# MCU_-_STM32F407VGT6.net
KiCad netlist of a schematic drawn in Altium Designer
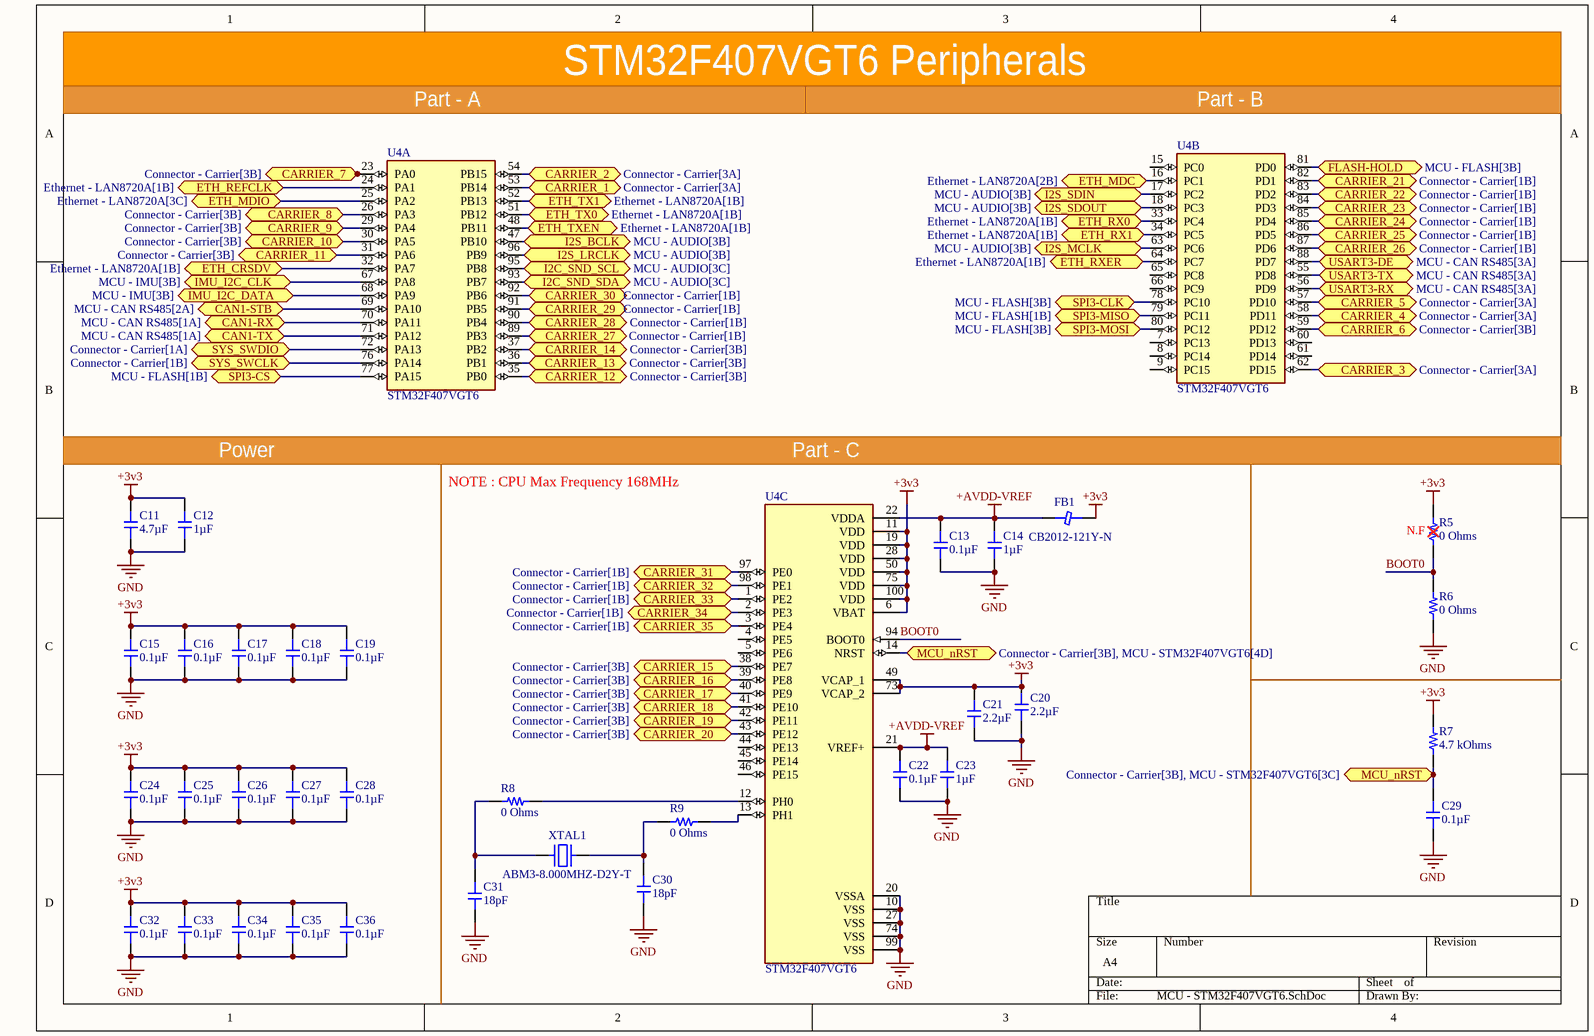
[diagram p0: MCU - STM32F407VGT6.SchDoc]

(export (version "E")
  (design (tool "Eeschema 10.0.6"))
  (components
    (comp (ref "C11")
      (value "4.7µF")
      (footprint "0603_Footprint")
      (description "4.7uF 0603 Surface Capacitor")
      (libsource (lib "MainLibrary") (part "4.7uF 0603 Surface Capacitor"))
    )
    (comp (ref "C12")
      (value "1µF")
      (footprint "0603_Footprint")
      (description "1uF 0603 Surface Capacitor")
      (libsource (lib "MainLibrary") (part "1uF 0603 Surface Capacitor"))
    )
    (comp (ref "C13")
      (value "0.1µF")
      (footprint "0603_Footprint")
      (description "0.1uF 0603 Surface Capacitor")
      (libsource (lib "MainLibrary") (part "0.1uF 0603 Surface Capacitor"))
    )
    (comp (ref "C14")
      (value "1µF")
      (footprint "0603_Footprint")
      (description "1uF 0603 Surface Capacitor")
      (libsource (lib "MainLibrary") (part "1uF 0603 Surface Capacitor"))
    )
    (comp (ref "C15")
      (value "0.1µF")
      (footprint "0603_Footprint")
      (description "0.1uF 0603 Surface Capacitor")
      (libsource (lib "MainLibrary") (part "0.1uF 0603 Surface Capacitor"))
    )
    (comp (ref "C16")
      (value "0.1µF")
      (footprint "0603_Footprint")
      (description "0.1uF 0603 Surface Capacitor")
      (libsource (lib "MainLibrary") (part "0.1uF 0603 Surface Capacitor"))
    )
    (comp (ref "C17")
      (value "0.1µF")
      (footprint "0603_Footprint")
      (description "0.1uF 0603 Surface Capacitor")
      (libsource (lib "MainLibrary") (part "0.1uF 0603 Surface Capacitor"))
    )
    (comp (ref "C18")
      (value "0.1µF")
      (footprint "0603_Footprint")
      (description "0.1uF 0603 Surface Capacitor")
      (libsource (lib "MainLibrary") (part "0.1uF 0603 Surface Capacitor"))
    )
    (comp (ref "C19")
      (value "0.1µF")
      (footprint "0603_Footprint")
      (description "0.1uF 0603 Surface Capacitor")
      (libsource (lib "MainLibrary") (part "0.1uF 0603 Surface Capacitor"))
    )
    (comp (ref "C20")
      (value "2.2µF")
      (footprint "0603_Footprint")
      (description "2.2uF 0603 Surface Capacitor")
      (libsource (lib "MainLibrary") (part "2.2uF 0603 Surface Capacitor"))
    )
    (comp (ref "C21")
      (value "2.2µF")
      (footprint "0603_Footprint")
      (description "2.2uF 0603 Surface Capacitor")
      (libsource (lib "MainLibrary") (part "2.2uF 0603 Surface Capacitor"))
    )
    (comp (ref "C22")
      (value "0.1µF")
      (footprint "0603_Footprint")
      (description "0.1uF 0603 Surface Capacitor")
      (libsource (lib "MainLibrary") (part "0.1uF 0603 Surface Capacitor"))
    )
    (comp (ref "C23")
      (value "1µF")
      (footprint "0603_Footprint")
      (description "1uF 0603 Surface Capacitor")
      (libsource (lib "MainLibrary") (part "1uF 0603 Surface Capacitor"))
    )
    (comp (ref "C24")
      (value "0.1µF")
      (footprint "0603_Footprint")
      (description "0.1uF 0603 Surface Capacitor")
      (libsource (lib "MainLibrary") (part "0.1uF 0603 Surface Capacitor"))
    )
    (comp (ref "C25")
      (value "0.1µF")
      (footprint "0603_Footprint")
      (description "0.1uF 0603 Surface Capacitor")
      (libsource (lib "MainLibrary") (part "0.1uF 0603 Surface Capacitor"))
    )
    (comp (ref "C26")
      (value "0.1µF")
      (footprint "0603_Footprint")
      (description "0.1uF 0603 Surface Capacitor")
      (libsource (lib "MainLibrary") (part "0.1uF 0603 Surface Capacitor"))
    )
    (comp (ref "C27")
      (value "0.1µF")
      (footprint "0603_Footprint")
      (description "0.1uF 0603 Surface Capacitor")
      (libsource (lib "MainLibrary") (part "0.1uF 0603 Surface Capacitor"))
    )
    (comp (ref "C28")
      (value "0.1µF")
      (footprint "0603_Footprint")
      (description "0.1uF 0603 Surface Capacitor")
      (libsource (lib "MainLibrary") (part "0.1uF 0603 Surface Capacitor"))
    )
    (comp (ref "C29")
      (value "0.1µF")
      (footprint "0603_Footprint")
      (description "0.1uF 0603 Surface Capacitor")
      (libsource (lib "MainLibrary") (part "0.1uF 0603 Surface Capacitor"))
    )
    (comp (ref "C30")
      (value "18pF")
      (footprint "0603_Footprint")
      (description "18pF 0603 Surface Capacitor")
      (libsource (lib "MainLibrary") (part "18pF 0603 Surface Capacitor"))
    )
    (comp (ref "C31")
      (value "18pF")
      (footprint "0603_Footprint")
      (description "18pF 0603 Surface Capacitor")
      (libsource (lib "MainLibrary") (part "18pF 0603 Surface Capacitor"))
    )
    (comp (ref "C32")
      (value "0.1µF")
      (footprint "0603_Footprint")
      (description "0.1uF 0603 Surface Capacitor")
      (libsource (lib "MainLibrary") (part "0.1uF 0603 Surface Capacitor"))
    )
    (comp (ref "C33")
      (value "0.1µF")
      (footprint "0603_Footprint")
      (description "0.1uF 0603 Surface Capacitor")
      (libsource (lib "MainLibrary") (part "0.1uF 0603 Surface Capacitor"))
    )
    (comp (ref "C34")
      (value "0.1µF")
      (footprint "0603_Footprint")
      (description "0.1uF 0603 Surface Capacitor")
      (libsource (lib "MainLibrary") (part "0.1uF 0603 Surface Capacitor"))
    )
    (comp (ref "C35")
      (value "0.1µF")
      (footprint "0603_Footprint")
      (description "0.1uF 0603 Surface Capacitor")
      (libsource (lib "MainLibrary") (part "0.1uF 0603 Surface Capacitor"))
    )
    (comp (ref "C36")
      (value "0.1µF")
      (footprint "0603_Footprint")
      (description "0.1uF 0603 Surface Capacitor")
      (libsource (lib "MainLibrary") (part "0.1uF 0603 Surface Capacitor"))
    )
    (comp (ref "FB1")
      (value "CB2012-121Y-N")
      (footprint "Inductor-0603")
      (libsource (lib "MainLibrary") (part "CB2012-121Y-N"))
    )
    (comp (ref "R5")
      (value "0 Ohms")
      (footprint "0603_RES")
      (description "0 Ohm 0603")
      (libsource (lib "MainLibrary") (part "0 Ohm 0603"))
    )
    (comp (ref "R6")
      (value "0 Ohms")
      (footprint "0603_RES")
      (description "0 Ohm 0603")
      (libsource (lib "MainLibrary") (part "0 Ohm 0603"))
    )
    (comp (ref "R7")
      (value "4.7 kOhms")
      (footprint "0603_RES")
      (description "4.7 kOhms 0603")
      (libsource (lib "MainLibrary") (part "4.7 kOhms 0603"))
    )
    (comp (ref "R8")
      (value "0 Ohms")
      (footprint "0603_RES")
      (description "0 Ohm 0603")
      (libsource (lib "MainLibrary") (part "0 Ohm 0603"))
    )
    (comp (ref "R9")
      (value "0 Ohms")
      (footprint "0603_RES")
      (description "0 Ohm 0603")
      (libsource (lib "MainLibrary") (part "0 Ohm 0603"))
    )
    (comp (ref "U4")
      (value "STM32F407VGT6")
      (footprint "QFP50P1600X1600X160-100N")
      (description "STM32 Series 32-bit 1 MB Flash 192 kB RAM ARM Based Microcontroller - LQFP-100")
      (libsource (lib "MainLibrary") (part "STM32F407VGT6"))
    )
    (comp (ref "XTAL1")
      (value "ABM3-8.000MHZ-D2Y-T")
      (footprint "ABM3")
      (description "Crystal or Oscillator")
      (fields (field (name "MOUSER PART NUMBER") "815-ABM3-8-D2Y-T"))
      (libsource (lib "MainLibrary") (part "ABM3-8.000MHZ-D2Y-T"))
    )
  )
  (nets
    (net (code "1") (name "+3v3") (class "Default")
      (node (ref "C11") (pin "1") (pinfunction "1_1") (pintype "passive"))
      (node (ref "C12") (pin "1") (pinfunction "1_1") (pintype "passive"))
      (node (ref "C15") (pin "1") (pinfunction "1_1") (pintype "passive"))
      (node (ref "C16") (pin "1") (pinfunction "1_1") (pintype "passive"))
      (node (ref "C17") (pin "1") (pinfunction "1_1") (pintype "passive"))
      (node (ref "C18") (pin "1") (pinfunction "1_1") (pintype "passive"))
      (node (ref "C19") (pin "1") (pinfunction "1_1") (pintype "passive"))
      (node (ref "C20") (pin "1") (pinfunction "1_1") (pintype "passive"))
      (node (ref "C21") (pin "1") (pinfunction "1_1") (pintype "passive"))
      (node (ref "C24") (pin "1") (pinfunction "1_1") (pintype "passive"))
      (node (ref "C25") (pin "1") (pinfunction "1_1") (pintype "passive"))
      (node (ref "C26") (pin "1") (pinfunction "1_1") (pintype "passive"))
      (node (ref "C27") (pin "1") (pinfunction "1_1") (pintype "passive"))
      (node (ref "C28") (pin "1") (pinfunction "1_1") (pintype "passive"))
      (node (ref "C32") (pin "1") (pinfunction "1_1") (pintype "passive"))
      (node (ref "C33") (pin "1") (pinfunction "1_1") (pintype "passive"))
      (node (ref "C34") (pin "1") (pinfunction "1_1") (pintype "passive"))
      (node (ref "C35") (pin "1") (pinfunction "1_1") (pintype "passive"))
      (node (ref "C36") (pin "1") (pinfunction "1_1") (pintype "passive"))
      (node (ref "FB1") (pin "2") (pinfunction "2_2") (pintype "passive"))
      (node (ref "R5") (pin "2") (pinfunction "2_2") (pintype "passive"))
      (node (ref "R7") (pin "2") (pinfunction "2_2") (pintype "passive"))
      (node (ref "U4") (pin "100") (pinfunction "VDD_100") (pintype "power_in"))
      (node (ref "U4") (pin "11") (pinfunction "VDD_11") (pintype "power_in"))
      (node (ref "U4") (pin "19") (pinfunction "VDD_19") (pintype "power_in"))
      (node (ref "U4") (pin "28") (pinfunction "VDD_28") (pintype "power_in"))
      (node (ref "U4") (pin "49") (pinfunction "VCAP_1_49") (pintype "passive"))
      (node (ref "U4") (pin "50") (pinfunction "VDD_50") (pintype "power_in"))
      (node (ref "U4") (pin "6") (pinfunction "VBAT_6") (pintype "power_in"))
      (node (ref "U4") (pin "73") (pinfunction "VCAP_2_73") (pintype "passive"))
      (node (ref "U4") (pin "75") (pinfunction "VDD_75") (pintype "power_in"))
    )
    (net (code "2") (name "+AVDD-VREF") (class "Default")
      (node (ref "C13") (pin "1") (pinfunction "1_1") (pintype "passive"))
      (node (ref "C14") (pin "1") (pinfunction "1_1") (pintype "passive"))
      (node (ref "C22") (pin "1") (pinfunction "1_1") (pintype "passive"))
      (node (ref "C23") (pin "1") (pinfunction "1_1") (pintype "passive"))
      (node (ref "FB1") (pin "1") (pinfunction "1_1") (pintype "passive"))
      (node (ref "U4") (pin "21") (pinfunction "VREF+_21") (pintype "power_in"))
      (node (ref "U4") (pin "22") (pinfunction "VDDA_22") (pintype "power_in"))
    )
    (net (code "3") (name "/BOOT0") (class "Default")
      (node (ref "R5") (pin "1") (pinfunction "1_1") (pintype "passive"))
      (node (ref "R6") (pin "2") (pinfunction "2_2") (pintype "passive"))
      (node (ref "U4") (pin "94") (pinfunction "BOOT0_94") (pintype "input"))
    )
    (net (code "4") (name "/CAN1-RX") (class "Default")
      (node (ref "U4") (pin "70") (pinfunction "PA11_70") (pintype "bidirectional"))
    )
    (net (code "5") (name "/CAN1-STB") (class "Default")
      (node (ref "U4") (pin "69") (pinfunction "PA10_69") (pintype "bidirectional"))
    )
    (net (code "6") (name "/CAN1-TX") (class "Default")
      (node (ref "U4") (pin "71") (pinfunction "PA12_71") (pintype "bidirectional"))
    )
    (net (code "7") (name "/CARRIER_1") (class "Default")
      (node (ref "U4") (pin "53") (pinfunction "PB14_53") (pintype "bidirectional"))
    )
    (net (code "8") (name "/CARRIER_2") (class "Default")
      (node (ref "U4") (pin "54") (pinfunction "PB15_54") (pintype "bidirectional"))
    )
    (net (code "9") (name "/CARRIER_3") (class "Default")
      (node (ref "U4") (pin "62") (pinfunction "PD15_62") (pintype "bidirectional"))
    )
    (net (code "10") (name "/CARRIER_4") (class "Default")
      (node (ref "U4") (pin "58") (pinfunction "PD11_58") (pintype "bidirectional"))
    )
    (net (code "11") (name "/CARRIER_5") (class "Default")
      (node (ref "U4") (pin "57") (pinfunction "PD10_57") (pintype "bidirectional"))
    )
    (net (code "12") (name "/CARRIER_6") (class "Default")
      (node (ref "U4") (pin "59") (pinfunction "PD12_59") (pintype "bidirectional"))
    )
    (net (code "13") (name "/CARRIER_7") (class "Default")
      (node (ref "U4") (pin "23") (pinfunction "PA0_23") (pintype "bidirectional"))
    )
    (net (code "14") (name "/CARRIER_8") (class "Default")
      (node (ref "U4") (pin "26") (pinfunction "PA3_26") (pintype "bidirectional"))
    )
    (net (code "15") (name "/CARRIER_9") (class "Default")
      (node (ref "U4") (pin "29") (pinfunction "PA4_29") (pintype "bidirectional"))
    )
    (net (code "16") (name "/CARRIER_10") (class "Default")
      (node (ref "U4") (pin "30") (pinfunction "PA5_30") (pintype "bidirectional"))
    )
    (net (code "17") (name "/CARRIER_11") (class "Default")
      (node (ref "U4") (pin "31") (pinfunction "PA6_31") (pintype "bidirectional"))
    )
    (net (code "18") (name "/CARRIER_12") (class "Default")
      (node (ref "U4") (pin "35") (pinfunction "PB0_35") (pintype "bidirectional"))
    )
    (net (code "19") (name "/CARRIER_13") (class "Default")
      (node (ref "U4") (pin "36") (pinfunction "PB1_36") (pintype "bidirectional"))
    )
    (net (code "20") (name "/CARRIER_14") (class "Default")
      (node (ref "U4") (pin "37") (pinfunction "PB2_37") (pintype "bidirectional"))
    )
    (net (code "21") (name "/CARRIER_15") (class "Default")
      (node (ref "U4") (pin "38") (pinfunction "PE7_38") (pintype "bidirectional"))
    )
    (net (code "22") (name "/CARRIER_16") (class "Default")
      (node (ref "U4") (pin "39") (pinfunction "PE8_39") (pintype "bidirectional"))
    )
    (net (code "23") (name "/CARRIER_17") (class "Default")
      (node (ref "U4") (pin "40") (pinfunction "PE9_40") (pintype "bidirectional"))
    )
    (net (code "24") (name "/CARRIER_18") (class "Default")
      (node (ref "U4") (pin "41") (pinfunction "PE10_41") (pintype "bidirectional"))
    )
    (net (code "25") (name "/CARRIER_19") (class "Default")
      (node (ref "U4") (pin "42") (pinfunction "PE11_42") (pintype "bidirectional"))
    )
    (net (code "26") (name "/CARRIER_20") (class "Default")
      (node (ref "U4") (pin "43") (pinfunction "PE12_43") (pintype "bidirectional"))
    )
    (net (code "27") (name "/CARRIER_21") (class "Default")
      (node (ref "U4") (pin "82") (pinfunction "PD1_82") (pintype "bidirectional"))
    )
    (net (code "28") (name "/CARRIER_22") (class "Default")
      (node (ref "U4") (pin "83") (pinfunction "PD2_83") (pintype "bidirectional"))
    )
    (net (code "29") (name "/CARRIER_23") (class "Default")
      (node (ref "U4") (pin "84") (pinfunction "PD3_84") (pintype "bidirectional"))
    )
    (net (code "30") (name "/CARRIER_24") (class "Default")
      (node (ref "U4") (pin "85") (pinfunction "PD4_85") (pintype "bidirectional"))
    )
    (net (code "31") (name "/CARRIER_25") (class "Default")
      (node (ref "U4") (pin "86") (pinfunction "PD5_86") (pintype "bidirectional"))
    )
    (net (code "32") (name "/CARRIER_26") (class "Default")
      (node (ref "U4") (pin "87") (pinfunction "PD6_87") (pintype "bidirectional"))
    )
    (net (code "33") (name "/CARRIER_27") (class "Default")
      (node (ref "U4") (pin "89") (pinfunction "PB3_89") (pintype "bidirectional"))
    )
    (net (code "34") (name "/CARRIER_28") (class "Default")
      (node (ref "U4") (pin "90") (pinfunction "PB4_90") (pintype "bidirectional"))
    )
    (net (code "35") (name "/CARRIER_29") (class "Default")
      (node (ref "U4") (pin "91") (pinfunction "PB5_91") (pintype "bidirectional"))
    )
    (net (code "36") (name "/CARRIER_30") (class "Default")
      (node (ref "U4") (pin "92") (pinfunction "PB6_92") (pintype "bidirectional"))
    )
    (net (code "37") (name "/CARRIER_31") (class "Default")
      (node (ref "U4") (pin "97") (pinfunction "PE0_97") (pintype "bidirectional"))
    )
    (net (code "38") (name "/CARRIER_32") (class "Default")
      (node (ref "U4") (pin "98") (pinfunction "PE1_98") (pintype "bidirectional"))
    )
    (net (code "39") (name "/CARRIER_33") (class "Default")
      (node (ref "U4") (pin "1") (pinfunction "PE2_1") (pintype "bidirectional"))
    )
    (net (code "40") (name "/CARRIER_34") (class "Default")
      (node (ref "U4") (pin "2") (pinfunction "PE3_2") (pintype "bidirectional"))
    )
    (net (code "41") (name "/CARRIER_35") (class "Default")
      (node (ref "U4") (pin "3") (pinfunction "PE4_3") (pintype "bidirectional"))
    )
    (net (code "42") (name "/ETH_CRSDV") (class "Default")
      (node (ref "U4") (pin "32") (pinfunction "PA7_32") (pintype "bidirectional"))
    )
    (net (code "43") (name "/ETH_MDC") (class "Default")
      (node (ref "U4") (pin "16") (pinfunction "PC1_16") (pintype "bidirectional"))
    )
    (net (code "44") (name "/ETH_MDIO") (class "Default")
      (node (ref "U4") (pin "25") (pinfunction "PA2_25") (pintype "bidirectional"))
    )
    (net (code "45") (name "/ETH_REFCLK") (class "Default")
      (node (ref "U4") (pin "24") (pinfunction "PA1_24") (pintype "bidirectional"))
    )
    (net (code "46") (name "/ETH_RX0") (class "Default")
      (node (ref "U4") (pin "33") (pinfunction "PC4_33") (pintype "bidirectional"))
    )
    (net (code "47") (name "/ETH_RX1") (class "Default")
      (node (ref "U4") (pin "34") (pinfunction "PC5_34") (pintype "bidirectional"))
    )
    (net (code "48") (name "/ETH_RXER") (class "Default")
      (node (ref "U4") (pin "64") (pinfunction "PC7_64") (pintype "bidirectional"))
    )
    (net (code "49") (name "/ETH_TX0") (class "Default")
      (node (ref "U4") (pin "51") (pinfunction "PB12_51") (pintype "bidirectional"))
    )
    (net (code "50") (name "/ETH_TX1") (class "Default")
      (node (ref "U4") (pin "52") (pinfunction "PB13_52") (pintype "bidirectional"))
    )
    (net (code "51") (name "/ETH_TXEN") (class "Default")
      (node (ref "U4") (pin "48") (pinfunction "PB11_48") (pintype "bidirectional"))
    )
    (net (code "52") (name "/FLASH-HOLD") (class "Default")
      (node (ref "U4") (pin "81") (pinfunction "PD0_81") (pintype "bidirectional"))
    )
    (net (code "53") (name "/I2C_SND_SCL") (class "Default")
      (node (ref "U4") (pin "95") (pinfunction "PB8_95") (pintype "bidirectional"))
    )
    (net (code "54") (name "/I2C_SND_SDA") (class "Default")
      (node (ref "U4") (pin "93") (pinfunction "PB7_93") (pintype "bidirectional"))
    )
    (net (code "55") (name "/I2S_BCLK") (class "Default")
      (node (ref "U4") (pin "47") (pinfunction "PB10_47") (pintype "bidirectional"))
    )
    (net (code "56") (name "/I2S_LRCLK") (class "Default")
      (node (ref "U4") (pin "96") (pinfunction "PB9_96") (pintype "bidirectional"))
    )
    (net (code "57") (name "/I2S_MCLK") (class "Default")
      (node (ref "U4") (pin "63") (pinfunction "PC6_63") (pintype "bidirectional"))
    )
    (net (code "58") (name "/I2S_SDIN") (class "Default")
      (node (ref "U4") (pin "17") (pinfunction "PC2_17") (pintype "bidirectional"))
    )
    (net (code "59") (name "/I2S_SDOUT") (class "Default")
      (node (ref "U4") (pin "18") (pinfunction "PC3_18") (pintype "bidirectional"))
    )
    (net (code "60") (name "/IMU_I2C_CLK") (class "Default")
      (node (ref "U4") (pin "67") (pinfunction "PA8_67") (pintype "bidirectional"))
    )
    (net (code "61") (name "/IMU_I2C_DATA") (class "Default")
      (node (ref "U4") (pin "68") (pinfunction "PA9_68") (pintype "bidirectional"))
    )
    (net (code "62") (name "/MCU_nRST") (class "Default")
      (node (ref "C29") (pin "1") (pinfunction "1_1") (pintype "passive"))
      (node (ref "R7") (pin "1") (pinfunction "1_1") (pintype "passive"))
      (node (ref "U4") (pin "14") (pinfunction "NRST_14") (pintype "bidirectional"))
    )
    (net (code "63") (name "/SPI3-CLK") (class "Default")
      (node (ref "U4") (pin "78") (pinfunction "PC10_78") (pintype "bidirectional"))
    )
    (net (code "64") (name "/SPI3-CS") (class "Default")
      (node (ref "U4") (pin "77") (pinfunction "PA15_77") (pintype "bidirectional"))
    )
    (net (code "65") (name "/SPI3-MISO") (class "Default")
      (node (ref "U4") (pin "79") (pinfunction "PC11_79") (pintype "bidirectional"))
    )
    (net (code "66") (name "/SPI3-MOSI") (class "Default")
      (node (ref "U4") (pin "80") (pinfunction "PC12_80") (pintype "bidirectional"))
    )
    (net (code "67") (name "/SYS_SWCLK") (class "Default")
      (node (ref "U4") (pin "76") (pinfunction "PA14_76") (pintype "bidirectional"))
    )
    (net (code "68") (name "/SYS_SWDIO") (class "Default")
      (node (ref "U4") (pin "72") (pinfunction "PA13_72") (pintype "bidirectional"))
    )
    (net (code "69") (name "/USART3-DE") (class "Default")
      (node (ref "U4") (pin "88") (pinfunction "PD7_88") (pintype "bidirectional"))
    )
    (net (code "70") (name "/USART3-RX") (class "Default")
      (node (ref "U4") (pin "56") (pinfunction "PD9_56") (pintype "bidirectional"))
    )
    (net (code "71") (name "/USART3-TX") (class "Default")
      (node (ref "U4") (pin "55") (pinfunction "PD8_55") (pintype "bidirectional"))
    )
    (net (code "72") (name "GND") (class "Default")
      (node (ref "C11") (pin "2") (pinfunction "2_2") (pintype "passive"))
      (node (ref "C12") (pin "2") (pinfunction "2_2") (pintype "passive"))
      (node (ref "C13") (pin "2") (pinfunction "2_2") (pintype "passive"))
      (node (ref "C14") (pin "2") (pinfunction "2_2") (pintype "passive"))
      (node (ref "C15") (pin "2") (pinfunction "2_2") (pintype "passive"))
      (node (ref "C16") (pin "2") (pinfunction "2_2") (pintype "passive"))
      (node (ref "C17") (pin "2") (pinfunction "2_2") (pintype "passive"))
      (node (ref "C18") (pin "2") (pinfunction "2_2") (pintype "passive"))
      (node (ref "C19") (pin "2") (pinfunction "2_2") (pintype "passive"))
      (node (ref "C20") (pin "2") (pinfunction "2_2") (pintype "passive"))
      (node (ref "C21") (pin "2") (pinfunction "2_2") (pintype "passive"))
      (node (ref "C22") (pin "2") (pinfunction "2_2") (pintype "passive"))
      (node (ref "C23") (pin "2") (pinfunction "2_2") (pintype "passive"))
      (node (ref "C24") (pin "2") (pinfunction "2_2") (pintype "passive"))
      (node (ref "C25") (pin "2") (pinfunction "2_2") (pintype "passive"))
      (node (ref "C26") (pin "2") (pinfunction "2_2") (pintype "passive"))
      (node (ref "C27") (pin "2") (pinfunction "2_2") (pintype "passive"))
      (node (ref "C28") (pin "2") (pinfunction "2_2") (pintype "passive"))
      (node (ref "C29") (pin "2") (pinfunction "2_2") (pintype "passive"))
      (node (ref "C30") (pin "2") (pinfunction "2_2") (pintype "passive"))
      (node (ref "C31") (pin "2") (pinfunction "2_2") (pintype "passive"))
      (node (ref "C32") (pin "2") (pinfunction "2_2") (pintype "passive"))
      (node (ref "C33") (pin "2") (pinfunction "2_2") (pintype "passive"))
      (node (ref "C34") (pin "2") (pinfunction "2_2") (pintype "passive"))
      (node (ref "C35") (pin "2") (pinfunction "2_2") (pintype "passive"))
      (node (ref "C36") (pin "2") (pinfunction "2_2") (pintype "passive"))
      (node (ref "R6") (pin "1") (pinfunction "1_1") (pintype "passive"))
      (node (ref "U4") (pin "10") (pinfunction "VSS_10") (pintype "power_in"))
      (node (ref "U4") (pin "20") (pinfunction "VSSA_20") (pintype "power_in"))
      (node (ref "U4") (pin "27") (pinfunction "VSS_27") (pintype "power_in"))
      (node (ref "U4") (pin "74") (pinfunction "VSS_74") (pintype "power_in"))
      (node (ref "U4") (pin "99") (pinfunction "VSS_99") (pintype "power_in"))
    )
    (net (code "73") (name "Net-(C30-Pad1)") (class "Default")
      (node (ref "C30") (pin "1") (pinfunction "1_1") (pintype "passive"))
      (node (ref "R9") (pin "1") (pinfunction "1_1") (pintype "passive"))
      (node (ref "XTAL1") (pin "2") (pinfunction "2_2") (pintype "passive"))
    )
    (net (code "74") (name "Net-(C31-Pad1)") (class "Default")
      (node (ref "C31") (pin "1") (pinfunction "1_1") (pintype "passive"))
      (node (ref "R8") (pin "1") (pinfunction "1_1") (pintype "passive"))
      (node (ref "XTAL1") (pin "1") (pinfunction "1_1") (pintype "passive"))
    )
    (net (code "75") (name "Net-(U4C-PH0)") (class "Default")
      (node (ref "R8") (pin "2") (pinfunction "2_2") (pintype "passive"))
      (node (ref "U4") (pin "12") (pinfunction "PH0_12") (pintype "bidirectional"))
    )
    (net (code "76") (name "Net-(U4C-PH1)") (class "Default")
      (node (ref "R9") (pin "2") (pinfunction "2_2") (pintype "passive"))
      (node (ref "U4") (pin "13") (pinfunction "PH1_13") (pintype "bidirectional"))
    )
    (net (code "77") (name "unconnected-(U4B-PC0-Pad15)") (class "Default")
      (node (ref "U4") (pin "15") (pinfunction "PC0_15") (pintype "bidirectional"))
    )
    (net (code "78") (name "unconnected-(U4B-PC8-Pad65)") (class "Default")
      (node (ref "U4") (pin "65") (pinfunction "PC8_65") (pintype "bidirectional"))
    )
    (net (code "79") (name "unconnected-(U4B-PC9-Pad66)") (class "Default")
      (node (ref "U4") (pin "66") (pinfunction "PC9_66") (pintype "bidirectional"))
    )
    (net (code "80") (name "unconnected-(U4B-PC13-Pad7)") (class "Default")
      (node (ref "U4") (pin "7") (pinfunction "PC13_7") (pintype "bidirectional"))
    )
    (net (code "81") (name "unconnected-(U4B-PC14-Pad8)") (class "Default")
      (node (ref "U4") (pin "8") (pinfunction "PC14_8") (pintype "bidirectional"))
    )
    (net (code "82") (name "unconnected-(U4B-PC15-Pad9)") (class "Default")
      (node (ref "U4") (pin "9") (pinfunction "PC15_9") (pintype "bidirectional"))
    )
    (net (code "83") (name "unconnected-(U4B-PD13-Pad60)") (class "Default")
      (node (ref "U4") (pin "60") (pinfunction "PD13_60") (pintype "bidirectional"))
    )
    (net (code "84") (name "unconnected-(U4B-PD14-Pad61)") (class "Default")
      (node (ref "U4") (pin "61") (pinfunction "PD14_61") (pintype "bidirectional"))
    )
    (net (code "85") (name "unconnected-(U4C-PE5-Pad4)") (class "Default")
      (node (ref "U4") (pin "4") (pinfunction "PE5_4") (pintype "bidirectional"))
    )
    (net (code "86") (name "unconnected-(U4C-PE6-Pad5)") (class "Default")
      (node (ref "U4") (pin "5") (pinfunction "PE6_5") (pintype "bidirectional"))
    )
    (net (code "87") (name "unconnected-(U4C-PE13-Pad44)") (class "Default")
      (node (ref "U4") (pin "44") (pinfunction "PE13_44") (pintype "bidirectional"))
    )
    (net (code "88") (name "unconnected-(U4C-PE14-Pad45)") (class "Default")
      (node (ref "U4") (pin "45") (pinfunction "PE14_45") (pintype "bidirectional"))
    )
    (net (code "89") (name "unconnected-(U4C-PE15-Pad46)") (class "Default")
      (node (ref "U4") (pin "46") (pinfunction "PE15_46") (pintype "bidirectional"))
    )
  )
)
